# fulladderripplerelay_version2.net
KiCad netlist of a schematic drawn in EAGLE
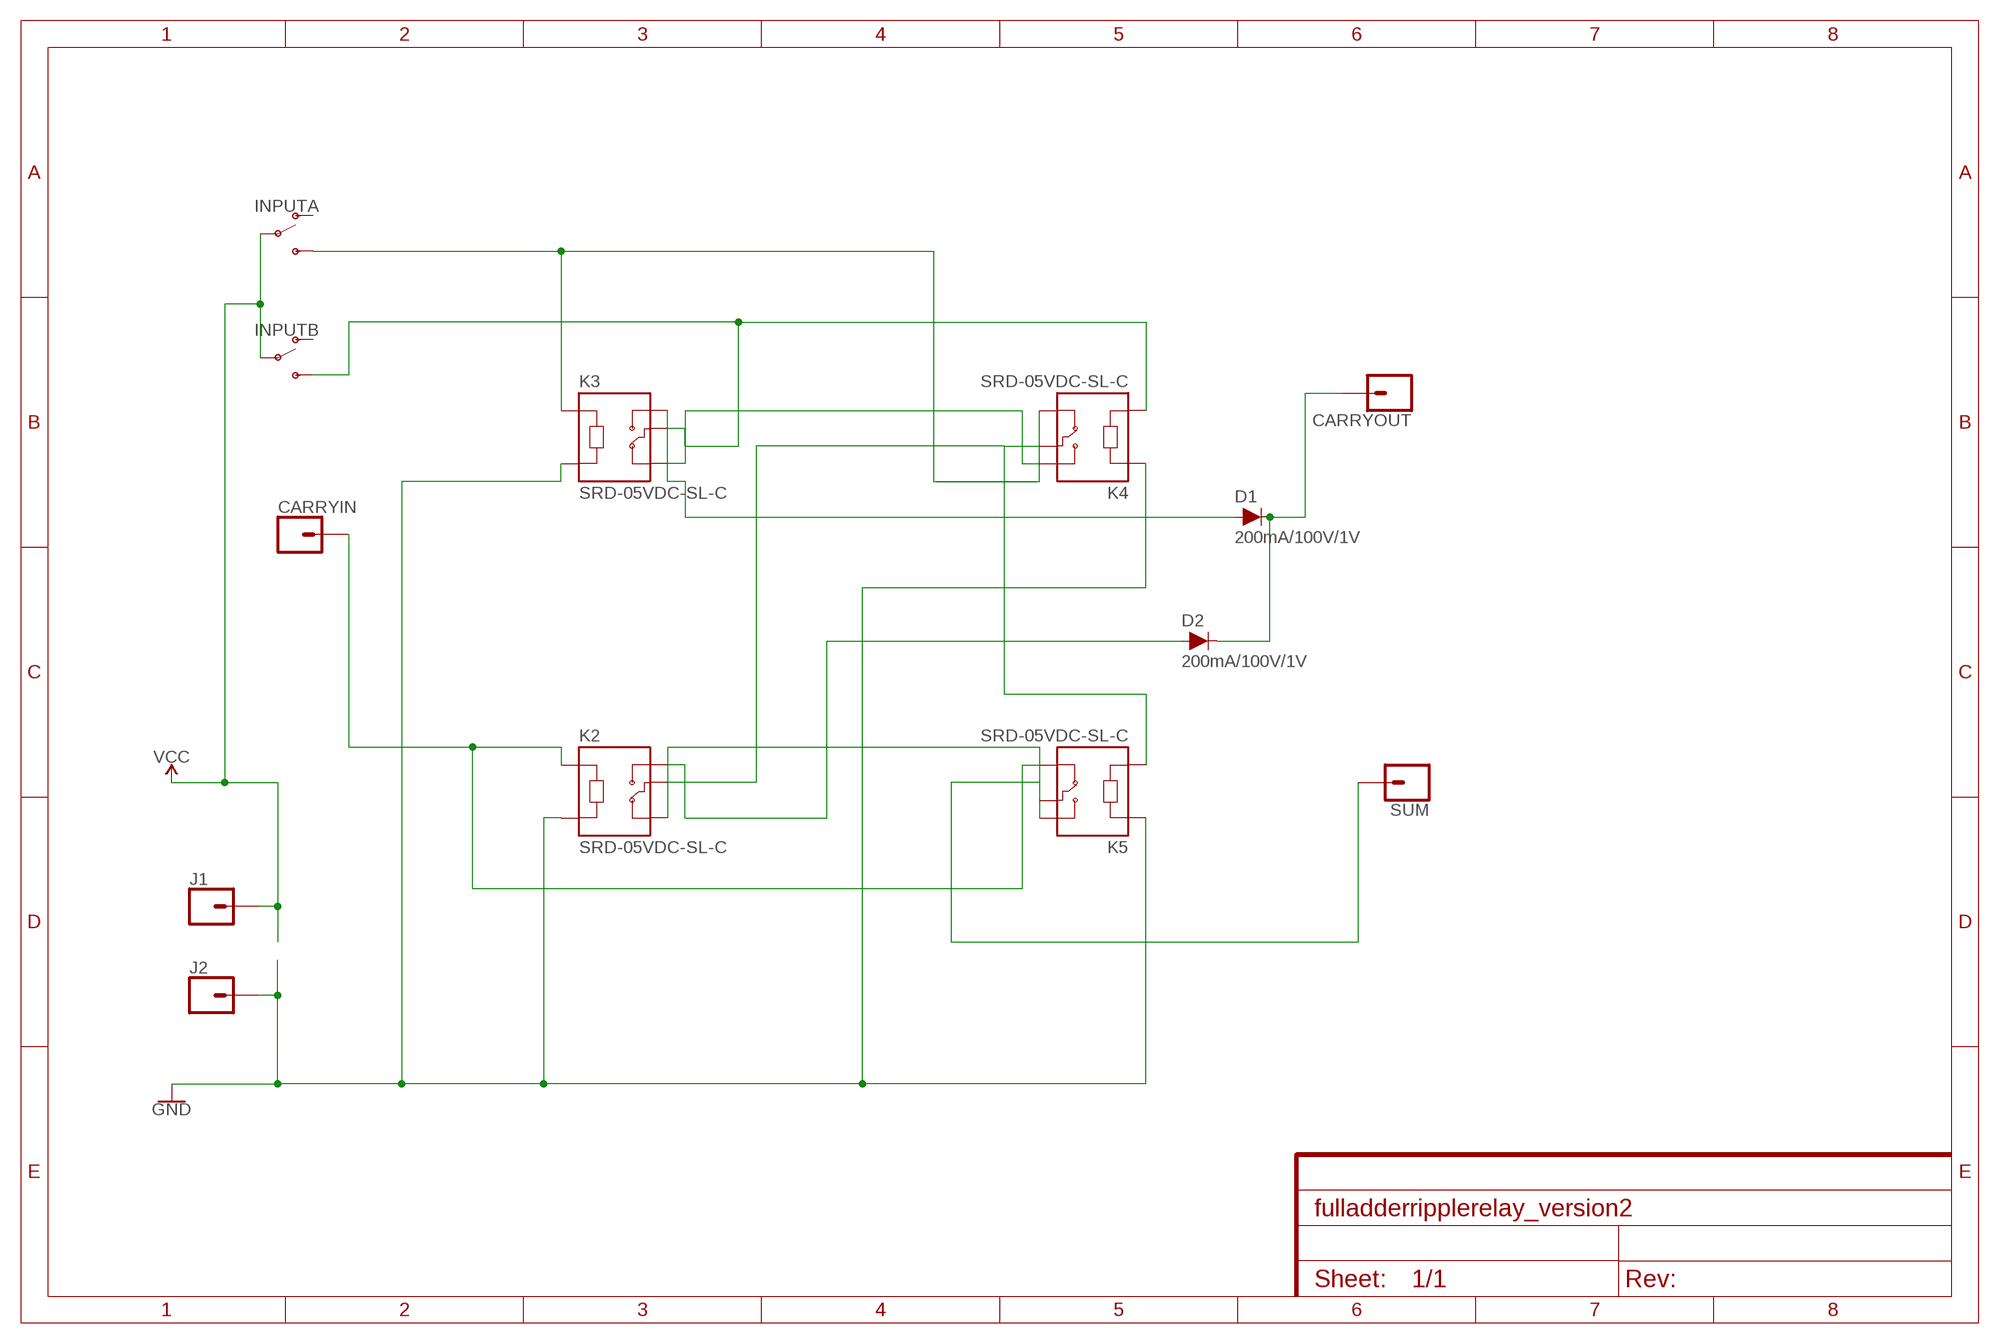
[diagram p0: schematic, sheet 1]

(export (version "E")
  (design (tool "Eeschema 10.0.6"))
  (components
    (comp (ref "CARRYIN")
      (value "CONN_01PTH_LONGPAD")
      (footprint "eagle-import:1X01_LONGPAD")
      (libsource (lib "eagle-import") (part "CONN_01PTH_LONGPAD"))
    )
    (comp (ref "CARRYOUT")
      (value "CONN_01PTH_LONGPAD")
      (footprint "eagle-import:1X01_LONGPAD")
      (libsource (lib "eagle-import") (part "CONN_01PTH_LONGPAD"))
    )
    (comp (ref "D1")
      (value "200mA/100V/1V")
      (footprint "eagle-import:DIODE-1N4148")
      (libsource (lib "eagle-import") (part "DIODE-1N4148"))
    )
    (comp (ref "D2")
      (value "200mA/100V/1V")
      (footprint "eagle-import:DIODE-1N4148")
      (libsource (lib "eagle-import") (part "DIODE-1N4148"))
    )
    (comp (ref "INPUTA")
      (value "SWITCH-SPDT-PTH-11.6X4.0MM")
      (footprint "eagle-import:SWITCH_SPDT_PTH_11.6X4.0MM")
      (libsource (lib "eagle-import") (part "SWITCH-SPDT-PTH-11.6X4.0MM"))
    )
    (comp (ref "INPUTB")
      (value "SWITCH-SPDT-PTH-11.6X4.0MM")
      (footprint "eagle-import:SWITCH_SPDT_PTH_11.6X4.0MM")
      (libsource (lib "eagle-import") (part "SWITCH-SPDT-PTH-11.6X4.0MM"))
    )
    (comp (ref "J1")
      (value "CONN_01PTH_LONGPAD")
      (footprint "eagle-import:1X01_LONGPAD")
      (libsource (lib "eagle-import") (part "CONN_01PTH_LONGPAD"))
    )
    (comp (ref "J2")
      (value "CONN_01PTH_LONGPAD")
      (footprint "eagle-import:1X01_LONGPAD")
      (libsource (lib "eagle-import") (part "CONN_01PTH_LONGPAD"))
    )
    (comp (ref "K2")
      (value "SRD-05VDC-SL-C")
      (footprint "eagle-import:RELAY_SRD-05VDC-SL-C")
      (fields (field (name "MF") "Songle Relay"))
      (libsource (lib "eagle-import") (part "SRD-05VDC-SL-C"))
    )
    (comp (ref "K3")
      (value "SRD-05VDC-SL-C")
      (footprint "eagle-import:RELAY_SRD-05VDC-SL-C")
      (fields (field (name "MF") "Songle Relay"))
      (libsource (lib "eagle-import") (part "SRD-05VDC-SL-C"))
    )
    (comp (ref "K4")
      (value "SRD-05VDC-SL-C")
      (footprint "eagle-import:RELAY_SRD-05VDC-SL-C")
      (fields (field (name "MF") "Songle Relay"))
      (libsource (lib "eagle-import") (part "SRD-05VDC-SL-C"))
    )
    (comp (ref "K5")
      (value "SRD-05VDC-SL-C")
      (footprint "eagle-import:RELAY_SRD-05VDC-SL-C")
      (fields (field (name "MF") "Songle Relay"))
      (libsource (lib "eagle-import") (part "SRD-05VDC-SL-C"))
    )
    (comp (ref "SUM")
      (value "CONN_01PTH_LONGPAD")
      (footprint "eagle-import:1X01_LONGPAD")
      (libsource (lib "eagle-import") (part "CONN_01PTH_LONGPAD"))
    )
  )
  (nets
    (net (code "1") (name "GND") (class "Default")
      (node (ref "J2") (pin "1") (pinfunction "1_1") (pintype "passive"))
      (node (ref "K2") (pin "A2") (pinfunction "A2_A2") (pintype "passive"))
      (node (ref "K3") (pin "A2") (pinfunction "A2_A2") (pintype "passive"))
      (node (ref "K4") (pin "A1") (pinfunction "A1_A1") (pintype "passive"))
      (node (ref "K5") (pin "A1") (pinfunction "A1_A1") (pintype "passive"))
    )
    (net (code "2") (name "Net-(CARRYIN-Pad1)") (class "Default")
      (node (ref "CARRYIN") (pin "1") (pinfunction "1_1") (pintype "passive"))
      (node (ref "K2") (pin "A1") (pinfunction "A1_A1") (pintype "passive"))
      (node (ref "K5") (pin "NC") (pinfunction "NC_NC") (pintype "passive"))
    )
    (net (code "3") (name "Net-(CARRYOUT-Pad1)") (class "Default")
      (node (ref "CARRYOUT") (pin "1") (pinfunction "1_1") (pintype "passive"))
      (node (ref "D1") (pin "C") (pinfunction "C_C") (pintype "passive"))
      (node (ref "D2") (pin "C") (pinfunction "C_C") (pintype "passive"))
    )
    (net (code "4") (name "Net-(D1-PadA)") (class "Default")
      (node (ref "D1") (pin "A") (pinfunction "A_A") (pintype "passive"))
      (node (ref "K3") (pin "NO") (pinfunction "NO_NO") (pintype "passive"))
    )
    (net (code "5") (name "Net-(D2-PadA)") (class "Default")
      (node (ref "D2") (pin "A") (pinfunction "A_A") (pintype "passive"))
      (node (ref "K2") (pin "NO") (pinfunction "NO_NO") (pintype "passive"))
    )
    (net (code "6") (name "Net-(INPUTA-S)") (class "Default")
      (node (ref "INPUTA") (pin "3") (pinfunction "S_3") (pintype "passive"))
      (node (ref "K3") (pin "A1") (pinfunction "A1_A1") (pintype "passive"))
      (node (ref "K4") (pin "NC") (pinfunction "NC_NC") (pintype "passive"))
    )
    (net (code "7") (name "Net-(INPUTB-S)") (class "Default")
      (node (ref "INPUTB") (pin "3") (pinfunction "S_3") (pintype "passive"))
      (node (ref "K3") (pin "COM") (pinfunction "COM_COM") (pintype "passive"))
      (node (ref "K4") (pin "A2") (pinfunction "A2_A2") (pintype "passive"))
    )
    (net (code "8") (name "Net-(K2-PadCOM)") (class "Default")
      (node (ref "K2") (pin "COM") (pinfunction "COM_COM") (pintype "passive"))
      (node (ref "K4") (pin "COM") (pinfunction "COM_COM") (pintype "passive"))
      (node (ref "K5") (pin "A2") (pinfunction "A2_A2") (pintype "passive"))
    )
    (net (code "9") (name "Net-(K2-PadNC)") (class "Default")
      (node (ref "K2") (pin "NC") (pinfunction "NC_NC") (pintype "passive"))
      (node (ref "K5") (pin "NO") (pinfunction "NO_NO") (pintype "passive"))
    )
    (net (code "10") (name "Net-(K3-PadNC)") (class "Default")
      (node (ref "K3") (pin "NC") (pinfunction "NC_NC") (pintype "passive"))
      (node (ref "K4") (pin "NO") (pinfunction "NO_NO") (pintype "passive"))
    )
    (net (code "11") (name "Net-(K5-PadCOM)") (class "Default")
      (node (ref "K5") (pin "COM") (pinfunction "COM_COM") (pintype "passive"))
      (node (ref "SUM") (pin "1") (pinfunction "1_1") (pintype "passive"))
    )
    (net (code "12") (name "VCC") (class "Default")
      (node (ref "INPUTA") (pin "2") (pinfunction "P_2") (pintype "passive"))
      (node (ref "INPUTB") (pin "2") (pinfunction "P_2") (pintype "passive"))
      (node (ref "J1") (pin "1") (pinfunction "1_1") (pintype "passive"))
    )
    (net (code "13") (name "unconnected-(INPUTA-O-Pad1)") (class "Default")
      (node (ref "INPUTA") (pin "1") (pinfunction "O_1") (pintype "passive"))
    )
    (net (code "14") (name "unconnected-(INPUTB-O-Pad1)") (class "Default")
      (node (ref "INPUTB") (pin "1") (pinfunction "O_1") (pintype "passive"))
    )
  )
)
